# MOSFETs.net
KiCad netlist of a schematic drawn in Altium Designer
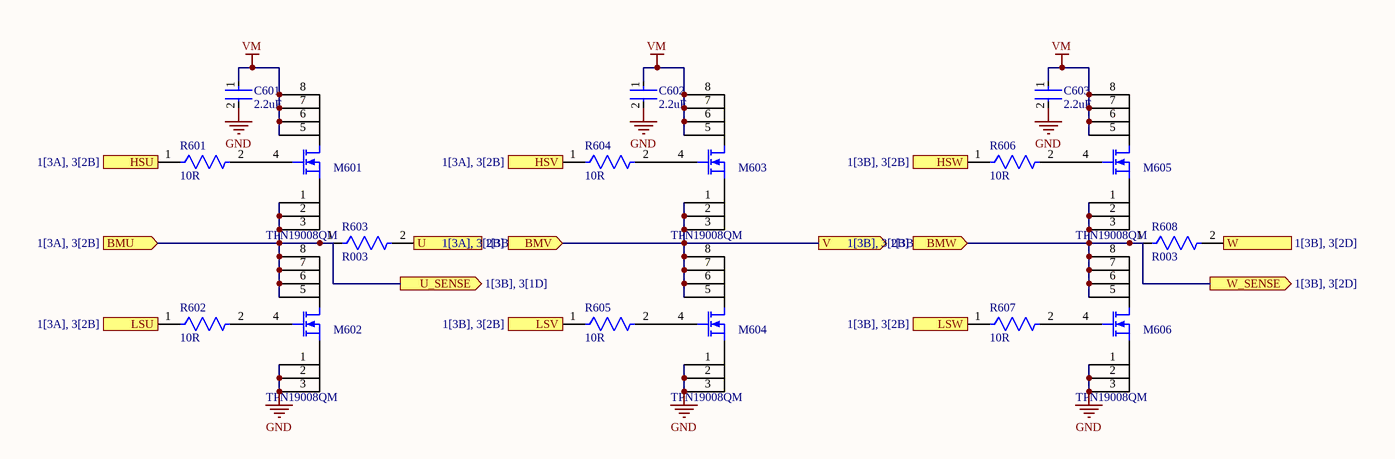
[diagram p0: MOSFETs.SchDoc]

(export (version "E")
  (design (tool "Eeschema 10.0.6"))
  (components
    (comp (ref "C601")
      (value "2.2uF")
      (footprint "FP-CL32-IPC_B")
      (description "Cap Ceramic 2.2uF 100V X7R ±10% SMD 1210 +125°C Embossed T/R")
      (fields (field (name "TOLERANCE") "10%") (field (name "VOLTAGE") "100V"))
      (libsource (lib "Altium Content Vault") (part "b4654b650e69147ec39a6b967a45e02"))
    )
    (comp (ref "C602")
      (value "2.2uF")
      (footprint "FP-CL32-IPC_B")
      (description "Cap Ceramic 2.2uF 100V X7R ±10% SMD 1210 +125°C Embossed T/R")
      (fields (field (name "TOLERANCE") "10%") (field (name "VOLTAGE") "100V"))
      (libsource (lib "Altium Content Vault") (part "b4654b650e69147ec39a6b967a45e02"))
    )
    (comp (ref "C603")
      (value "2.2uF")
      (footprint "FP-CL32-IPC_B")
      (description "Cap Ceramic 2.2uF 100V X7R ±10% SMD 1210 +125°C Embossed T/R")
      (fields (field (name "TOLERANCE") "10%") (field (name "VOLTAGE") "100V"))
      (libsource (lib "Altium Content Vault") (part "b4654b650e69147ec39a6b967a45e02"))
    )
    (comp (ref "M601")
      (value "TPN19008QM")
      (footprint "TSON Advance_TOS")
      (description "No Description Available")
      (libsource (lib "TPN19008QM") (part "TPN19008QM"))
    )
    (comp (ref "M602")
      (value "TPN19008QM")
      (footprint "TSON Advance_TOS")
      (description "No Description Available")
      (libsource (lib "TPN19008QM") (part "TPN19008QM"))
    )
    (comp (ref "M603")
      (value "TPN19008QM")
      (footprint "TSON Advance_TOS")
      (description "No Description Available")
      (libsource (lib "TPN19008QM") (part "TPN19008QM"))
    )
    (comp (ref "M604")
      (value "TPN19008QM")
      (footprint "TSON Advance_TOS")
      (description "No Description Available")
      (libsource (lib "TPN19008QM") (part "TPN19008QM"))
    )
    (comp (ref "M605")
      (value "TPN19008QM")
      (footprint "TSON Advance_TOS")
      (description "No Description Available")
      (libsource (lib "TPN19008QM") (part "TPN19008QM"))
    )
    (comp (ref "M606")
      (value "TPN19008QM")
      (footprint "TSON Advance_TOS")
      (description "No Description Available")
      (libsource (lib "TPN19008QM") (part "TPN19008QM"))
    )
    (comp (ref "R601")
      (value "10R")
      (footprint "FP-ERJ3EK-IPC_B")
      (description "RES SMD 10 OHM 1% 1/10W 0603")
      (fields
        (field (name "OCTOPART") "https://octopart.com/erj-3ekf10r0v-panasonic-55403649")
        (field (name "MANUFACTURER PART NUMBER") "ERJ-3EKF10R0V")
      )
      (libsource (lib "Altium Content Vault") (part "1029c3af85768c4190bb7ad29bc67b5"))
    )
    (comp (ref "R602")
      (value "10R")
      (footprint "FP-ERJ3EK-IPC_B")
      (description "RES SMD 10 OHM 1% 1/10W 0603")
      (fields
        (field (name "OCTOPART") "https://octopart.com/erj-3ekf10r0v-panasonic-55403649")
        (field (name "MANUFACTURER PART NUMBER") "ERJ-3EKF10R0V")
      )
      (libsource (lib "Altium Content Vault") (part "1029c3af85768c4190bb7ad29bc67b5"))
    )
    (comp (ref "R603")
      (value "R003")
      (footprint "FP-CRE2512-R001-R004-IPC_A")
      (description "RES 0.003 OHM 1% 3W 2512")
      (fields (field (name "TOLERANCE") "1%"))
      (libsource (lib "Altium Content Vault") (part "1029c3af85768c4190bb7ad29bc67b5"))
    )
    (comp (ref "R604")
      (value "10R")
      (footprint "FP-ERJ3EK-IPC_B")
      (description "RES SMD 10 OHM 1% 1/10W 0603")
      (fields
        (field (name "OCTOPART") "https://octopart.com/erj-3ekf10r0v-panasonic-55403649")
        (field (name "MANUFACTURER PART NUMBER") "ERJ-3EKF10R0V")
      )
      (libsource (lib "Altium Content Vault") (part "1029c3af85768c4190bb7ad29bc67b5"))
    )
    (comp (ref "R605")
      (value "10R")
      (footprint "FP-ERJ3EK-IPC_B")
      (description "RES SMD 10 OHM 1% 1/10W 0603")
      (fields
        (field (name "OCTOPART") "https://octopart.com/erj-3ekf10r0v-panasonic-55403649")
        (field (name "MANUFACTURER PART NUMBER") "ERJ-3EKF10R0V")
      )
      (libsource (lib "Altium Content Vault") (part "1029c3af85768c4190bb7ad29bc67b5"))
    )
    (comp (ref "R606")
      (value "10R")
      (footprint "FP-ERJ3EK-IPC_B")
      (description "RES SMD 10 OHM 1% 1/10W 0603")
      (fields
        (field (name "OCTOPART") "https://octopart.com/erj-3ekf10r0v-panasonic-55403649")
        (field (name "MANUFACTURER PART NUMBER") "ERJ-3EKF10R0V")
      )
      (libsource (lib "Altium Content Vault") (part "1029c3af85768c4190bb7ad29bc67b5"))
    )
    (comp (ref "R607")
      (value "10R")
      (footprint "FP-ERJ3EK-IPC_B")
      (description "RES SMD 10 OHM 1% 1/10W 0603")
      (fields
        (field (name "OCTOPART") "https://octopart.com/erj-3ekf10r0v-panasonic-55403649")
        (field (name "MANUFACTURER PART NUMBER") "ERJ-3EKF10R0V")
      )
      (libsource (lib "Altium Content Vault") (part "1029c3af85768c4190bb7ad29bc67b5"))
    )
    (comp (ref "R608")
      (value "R003")
      (footprint "FP-CRE2512-R001-R004-IPC_A")
      (description "RES 0.003 OHM 1% 3W 2512")
      (fields (field (name "TOLERANCE") "1%"))
      (libsource (lib "Altium Content Vault") (part "1029c3af85768c4190bb7ad29bc67b5"))
    )
  )
  (nets
    (net (code "1") (name "/BMU") (class "Default")
      (node (ref "M601") (pin "1") (pinfunction "SOURCE_1") (pintype "passive"))
      (node (ref "M601") (pin "2") (pinfunction "SOURCE_2") (pintype "passive"))
      (node (ref "M601") (pin "3") (pinfunction "SOURCE_3") (pintype "passive"))
      (node (ref "M602") (pin "5") (pinfunction "DRAIN_5") (pintype "passive"))
      (node (ref "M602") (pin "6") (pinfunction "DRAIN_6") (pintype "passive"))
      (node (ref "M602") (pin "7") (pinfunction "DRAIN_7") (pintype "passive"))
      (node (ref "M602") (pin "8") (pinfunction "DRAIN_8") (pintype "passive"))
      (node (ref "R603") (pin "1") (pinfunction "1_1") (pintype "passive"))
    )
    (net (code "2") (name "/BMV") (class "Default")
      (node (ref "M603") (pin "1") (pinfunction "SOURCE_1") (pintype "passive"))
      (node (ref "M603") (pin "2") (pinfunction "SOURCE_2") (pintype "passive"))
      (node (ref "M603") (pin "3") (pinfunction "SOURCE_3") (pintype "passive"))
      (node (ref "M604") (pin "5") (pinfunction "DRAIN_5") (pintype "passive"))
      (node (ref "M604") (pin "6") (pinfunction "DRAIN_6") (pintype "passive"))
      (node (ref "M604") (pin "7") (pinfunction "DRAIN_7") (pintype "passive"))
      (node (ref "M604") (pin "8") (pinfunction "DRAIN_8") (pintype "passive"))
    )
    (net (code "3") (name "/BMW") (class "Default")
      (node (ref "M605") (pin "1") (pinfunction "SOURCE_1") (pintype "passive"))
      (node (ref "M605") (pin "2") (pinfunction "SOURCE_2") (pintype "passive"))
      (node (ref "M605") (pin "3") (pinfunction "SOURCE_3") (pintype "passive"))
      (node (ref "M606") (pin "5") (pinfunction "DRAIN_5") (pintype "passive"))
      (node (ref "M606") (pin "6") (pinfunction "DRAIN_6") (pintype "passive"))
      (node (ref "M606") (pin "7") (pinfunction "DRAIN_7") (pintype "passive"))
      (node (ref "M606") (pin "8") (pinfunction "DRAIN_8") (pintype "passive"))
      (node (ref "R608") (pin "1") (pinfunction "1_1") (pintype "passive"))
    )
    (net (code "4") (name "/HSU") (class "Default")
      (node (ref "R601") (pin "1") (pinfunction "1_1") (pintype "passive"))
    )
    (net (code "5") (name "/HSV") (class "Default")
      (node (ref "R604") (pin "1") (pinfunction "1_1") (pintype "passive"))
    )
    (net (code "6") (name "/HSW") (class "Default")
      (node (ref "R606") (pin "1") (pinfunction "1_1") (pintype "passive"))
    )
    (net (code "7") (name "/LSU") (class "Default")
      (node (ref "R602") (pin "1") (pinfunction "1_1") (pintype "passive"))
    )
    (net (code "8") (name "/LSV") (class "Default")
      (node (ref "R605") (pin "1") (pinfunction "1_1") (pintype "passive"))
    )
    (net (code "9") (name "/LSW") (class "Default")
      (node (ref "R607") (pin "1") (pinfunction "1_1") (pintype "passive"))
    )
    (net (code "10") (name "/U") (class "Default")
      (node (ref "R603") (pin "2") (pinfunction "2_2") (pintype "passive"))
    )
    (net (code "11") (name "/W") (class "Default")
      (node (ref "R608") (pin "2") (pinfunction "2_2") (pintype "passive"))
    )
    (net (code "12") (name "GND") (class "Default")
      (node (ref "C601") (pin "2") (pinfunction "2_2") (pintype "passive"))
      (node (ref "C602") (pin "2") (pinfunction "2_2") (pintype "passive"))
      (node (ref "C603") (pin "2") (pinfunction "2_2") (pintype "passive"))
      (node (ref "M602") (pin "1") (pinfunction "SOURCE_1") (pintype "passive"))
      (node (ref "M602") (pin "2") (pinfunction "SOURCE_2") (pintype "passive"))
      (node (ref "M602") (pin "3") (pinfunction "SOURCE_3") (pintype "passive"))
      (node (ref "M604") (pin "1") (pinfunction "SOURCE_1") (pintype "passive"))
      (node (ref "M604") (pin "2") (pinfunction "SOURCE_2") (pintype "passive"))
      (node (ref "M604") (pin "3") (pinfunction "SOURCE_3") (pintype "passive"))
      (node (ref "M606") (pin "1") (pinfunction "SOURCE_1") (pintype "passive"))
      (node (ref "M606") (pin "2") (pinfunction "SOURCE_2") (pintype "passive"))
      (node (ref "M606") (pin "3") (pinfunction "SOURCE_3") (pintype "passive"))
    )
    (net (code "13") (name "Net-(M601-GATE)") (class "Default")
      (node (ref "M601") (pin "4") (pinfunction "GATE_4") (pintype "passive"))
      (node (ref "R601") (pin "2") (pinfunction "2_2") (pintype "passive"))
    )
    (net (code "14") (name "Net-(M602-GATE)") (class "Default")
      (node (ref "M602") (pin "4") (pinfunction "GATE_4") (pintype "passive"))
      (node (ref "R602") (pin "2") (pinfunction "2_2") (pintype "passive"))
    )
    (net (code "15") (name "Net-(M603-GATE)") (class "Default")
      (node (ref "M603") (pin "4") (pinfunction "GATE_4") (pintype "passive"))
      (node (ref "R604") (pin "2") (pinfunction "2_2") (pintype "passive"))
    )
    (net (code "16") (name "Net-(M604-GATE)") (class "Default")
      (node (ref "M604") (pin "4") (pinfunction "GATE_4") (pintype "passive"))
      (node (ref "R605") (pin "2") (pinfunction "2_2") (pintype "passive"))
    )
    (net (code "17") (name "Net-(M605-GATE)") (class "Default")
      (node (ref "M605") (pin "4") (pinfunction "GATE_4") (pintype "passive"))
      (node (ref "R606") (pin "2") (pinfunction "2_2") (pintype "passive"))
    )
    (net (code "18") (name "Net-(M606-GATE)") (class "Default")
      (node (ref "M606") (pin "4") (pinfunction "GATE_4") (pintype "passive"))
      (node (ref "R607") (pin "2") (pinfunction "2_2") (pintype "passive"))
    )
    (net (code "19") (name "VM") (class "Default")
      (node (ref "C601") (pin "1") (pinfunction "1_1") (pintype "passive"))
      (node (ref "C602") (pin "1") (pinfunction "1_1") (pintype "passive"))
      (node (ref "C603") (pin "1") (pinfunction "1_1") (pintype "passive"))
      (node (ref "M601") (pin "5") (pinfunction "DRAIN_5") (pintype "passive"))
      (node (ref "M601") (pin "6") (pinfunction "DRAIN_6") (pintype "passive"))
      (node (ref "M601") (pin "7") (pinfunction "DRAIN_7") (pintype "passive"))
      (node (ref "M601") (pin "8") (pinfunction "DRAIN_8") (pintype "passive"))
      (node (ref "M603") (pin "5") (pinfunction "DRAIN_5") (pintype "passive"))
      (node (ref "M603") (pin "6") (pinfunction "DRAIN_6") (pintype "passive"))
      (node (ref "M603") (pin "7") (pinfunction "DRAIN_7") (pintype "passive"))
      (node (ref "M603") (pin "8") (pinfunction "DRAIN_8") (pintype "passive"))
      (node (ref "M605") (pin "5") (pinfunction "DRAIN_5") (pintype "passive"))
      (node (ref "M605") (pin "6") (pinfunction "DRAIN_6") (pintype "passive"))
      (node (ref "M605") (pin "7") (pinfunction "DRAIN_7") (pintype "passive"))
      (node (ref "M605") (pin "8") (pinfunction "DRAIN_8") (pintype "passive"))
    )
  )
)
